# RTD_Amplifier.net
KiCad netlist of a schematic drawn in Altium Designer
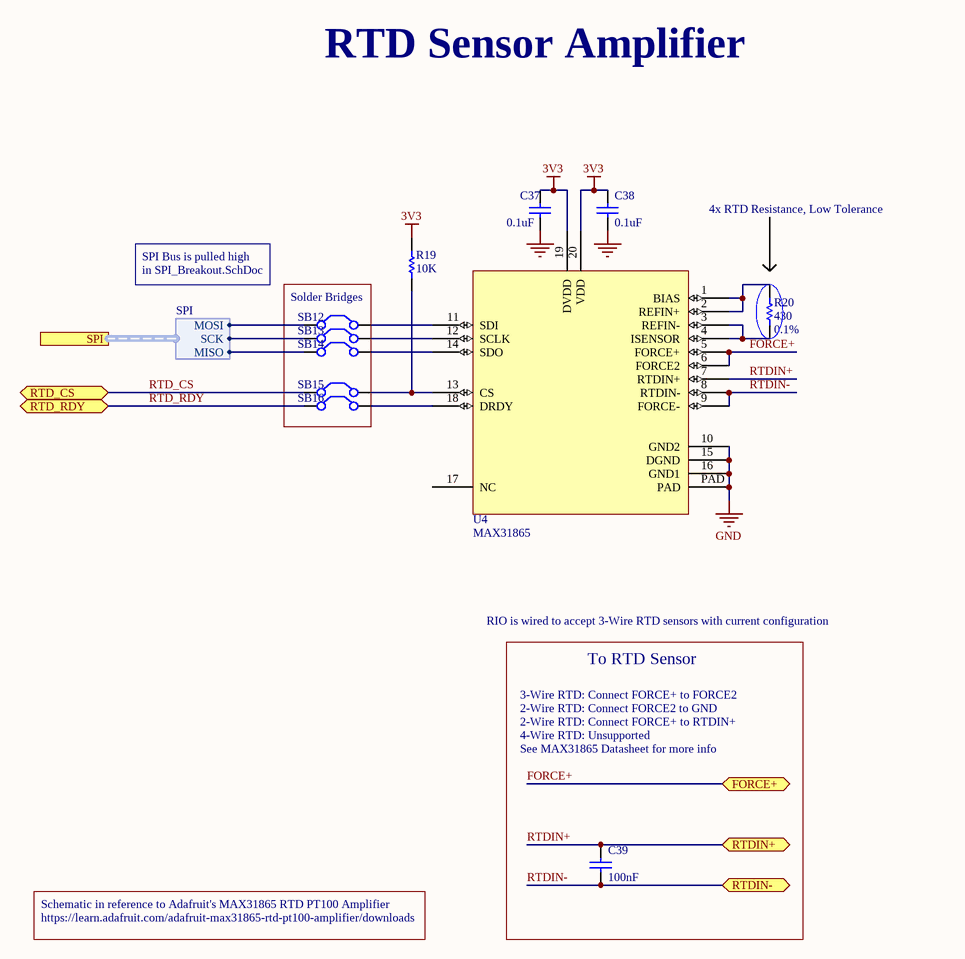
[diagram p0: RTD_Amplifier.SchDoc]

(export (version "E")
  (design (tool "Eeschema 10.0.6"))
  (components
    (comp (ref "C37")
      (value "0.1uF")
      (footprint "0402")
      (description "Capacitor")
      (fields (field (name "Comment") "Cap"))
      (libsource (lib "Miscellaneous Devices") (part "Cap"))
    )
    (comp (ref "C38")
      (value "0.1uF")
      (footprint "0402")
      (description "Capacitor")
      (fields (field (name "Comment") "Cap"))
      (libsource (lib "Miscellaneous Devices") (part "Cap"))
    )
    (comp (ref "C39")
      (value "100nF")
      (footprint "0402")
      (description "Capacitor")
      (fields (field (name "Comment") "Cap"))
      (libsource (lib "Miscellaneous Devices") (part "Cap"))
    )
    (comp (ref "R19")
      (value "10K")
      (footprint "0402")
      (description "Resistor")
      (fields (field (name "Comment") "Res1"))
      (libsource (lib "Miscellaneous Devices") (part "Res1"))
    )
    (comp (ref "R20")
      (value "430")
      (footprint "0402")
      (description "Resistor")
      (fields (field (name "TOLERANCE") "0.1%") (field (name "Comment") "Res1"))
      (libsource (lib "Miscellaneous Devices") (part "Res1"))
    )
    (comp (ref "SB12")
      (value "Jumper")
      (footprint "SB-2pos")
      (description "Jumper Wire")
      (libsource (lib "Miscellaneous Devices") (part "Jumper"))
    )
    (comp (ref "SB13")
      (value "Jumper")
      (footprint "SB-2pos")
      (description "Jumper Wire")
      (libsource (lib "Miscellaneous Devices") (part "Jumper"))
    )
    (comp (ref "SB14")
      (value "Jumper")
      (footprint "SB-2pos")
      (description "Jumper Wire")
      (libsource (lib "Miscellaneous Devices") (part "Jumper"))
    )
    (comp (ref "SB15")
      (value "Jumper")
      (footprint "SB-2pos")
      (description "Jumper Wire")
      (libsource (lib "Miscellaneous Devices") (part "Jumper"))
    )
    (comp (ref "SB16")
      (value "Jumper")
      (footprint "SB-2pos")
      (description "Jumper Wire")
      (libsource (lib "Miscellaneous Devices") (part "Jumper"))
    )
    (comp (ref "U4")
      (value "MAX31865")
      (footprint "TQFN20-EP-Maxim")
      (description "RTD Digital Converter")
      (fields
        (field (name "DIGIKEY PART NUMBER") "MAX31865ATP+-ND")
        (field (name "MANUFACTURER PART NUMBER") "MAX31865ATP+")
      )
      (libsource (lib "LaunchyRIOComponents") (part "MAX31865"))
    )
  )
  (nets
    (net (code "2") (name "/FORCE+") (class "Default")
      (node (ref "U4") (pin "5") (pinfunction "FORCE+_5") (pintype "bidirectional"))
      (node (ref "U4") (pin "6") (pinfunction "FORCE2_6") (pintype "bidirectional"))
    )
    (net (code "3") (name "/MISO") (class "Default")
      (node (ref "SB14") (pin "1") (pinfunction "C1_1") (pintype "passive"))
    )
    (net (code "4") (name "/MOSI") (class "Default")
      (node (ref "SB12") (pin "1") (pinfunction "C1_1") (pintype "passive"))
    )
    (net (code "5") (name "/RTDIN+") (class "Default")
      (node (ref "C39") (pin "2") (pinfunction "2_2") (pintype "passive"))
      (node (ref "U4") (pin "7") (pinfunction "RTDIN+_7") (pintype "bidirectional"))
    )
    (net (code "6") (name "/RTDIN-") (class "Default")
      (node (ref "C39") (pin "1") (pinfunction "1_1") (pintype "passive"))
      (node (ref "U4") (pin "8") (pinfunction "RTDIN-_8") (pintype "bidirectional"))
      (node (ref "U4") (pin "9") (pinfunction "FORCE-_9") (pintype "bidirectional"))
    )
    (net (code "7") (name "/RTD_CS") (class "Default")
      (node (ref "SB15") (pin "1") (pinfunction "C1_1") (pintype "passive"))
    )
    (net (code "8") (name "/RTD_RDY") (class "Default")
      (node (ref "SB16") (pin "1") (pinfunction "C1_1") (pintype "passive"))
    )
    (net (code "9") (name "/SCK") (class "Default")
      (node (ref "SB13") (pin "1") (pinfunction "C1_1") (pintype "passive"))
    )
    (net (code "11") (name "3V3") (class "Default")
      (node (ref "C37") (pin "2") (pinfunction "2_2") (pintype "passive"))
      (node (ref "C38") (pin "2") (pinfunction "2_2") (pintype "passive"))
      (node (ref "R19") (pin "1") (pinfunction "1_1") (pintype "passive"))
      (node (ref "U4") (pin "19") (pinfunction "DVDD_19") (pintype "power_in"))
      (node (ref "U4") (pin "20") (pinfunction "VDD_20") (pintype "power_in"))
    )
    (net (code "12") (name "GND") (class "Default")
      (node (ref "C37") (pin "1") (pinfunction "1_1") (pintype "passive"))
      (node (ref "C38") (pin "1") (pinfunction "1_1") (pintype "passive"))
      (node (ref "U4") (pin "10") (pinfunction "GND2_10") (pintype "power_in"))
      (node (ref "U4") (pin "15") (pinfunction "DGND_15") (pintype "power_in"))
      (node (ref "U4") (pin "16") (pinfunction "GND1_16") (pintype "power_in"))
      (node (ref "U4") (pin "PAD") (pinfunction "PAD_PAD") (pintype "power_in"))
    )
    (net (code "13") (name "Net-(SB12-C2)") (class "Default")
      (node (ref "SB12") (pin "2") (pinfunction "C2_2") (pintype "passive"))
      (node (ref "U4") (pin "11") (pinfunction "SDI_11") (pintype "bidirectional"))
    )
    (net (code "14") (name "Net-(SB13-C2)") (class "Default")
      (node (ref "SB13") (pin "2") (pinfunction "C2_2") (pintype "passive"))
      (node (ref "U4") (pin "12") (pinfunction "SCLK_12") (pintype "bidirectional"))
    )
    (net (code "15") (name "Net-(SB14-C2)") (class "Default")
      (node (ref "SB14") (pin "2") (pinfunction "C2_2") (pintype "passive"))
      (node (ref "U4") (pin "14") (pinfunction "SDO_14") (pintype "bidirectional"))
    )
    (net (code "16") (name "Net-(SB15-C2)") (class "Default")
      (node (ref "R19") (pin "2") (pinfunction "2_2") (pintype "passive"))
      (node (ref "SB15") (pin "2") (pinfunction "C2_2") (pintype "passive"))
      (node (ref "U4") (pin "13") (pinfunction "CS_13") (pintype "bidirectional"))
    )
    (net (code "17") (name "Net-(SB16-C2)") (class "Default")
      (node (ref "SB16") (pin "2") (pinfunction "C2_2") (pintype "passive"))
      (node (ref "U4") (pin "18") (pinfunction "DRDY_18") (pintype "bidirectional"))
    )
    (net (code "18") (name "Net-(U4-BIAS)") (class "Default")
      (node (ref "R20") (pin "1") (pinfunction "1_1") (pintype "passive"))
      (node (ref "U4") (pin "1") (pinfunction "BIAS_1") (pintype "bidirectional"))
      (node (ref "U4") (pin "2") (pinfunction "REFIN+_2") (pintype "bidirectional"))
    )
    (net (code "19") (name "Net-(U4-ISENSOR)") (class "Default")
      (node (ref "R20") (pin "2") (pinfunction "2_2") (pintype "passive"))
      (node (ref "U4") (pin "3") (pinfunction "REFIN-_3") (pintype "bidirectional"))
      (node (ref "U4") (pin "4") (pinfunction "ISENSOR_4") (pintype "bidirectional"))
    )
    (net (code "20") (name "unconnected-(U4-NC-Pad17)") (class "Default")
      (node (ref "U4") (pin "17") (pinfunction "NC_17") (pintype "passive"))
    )
  )
)
